# Adafruit_TPS61040_Boost_Converter.net
KiCad netlist of a schematic drawn in Altium Designer
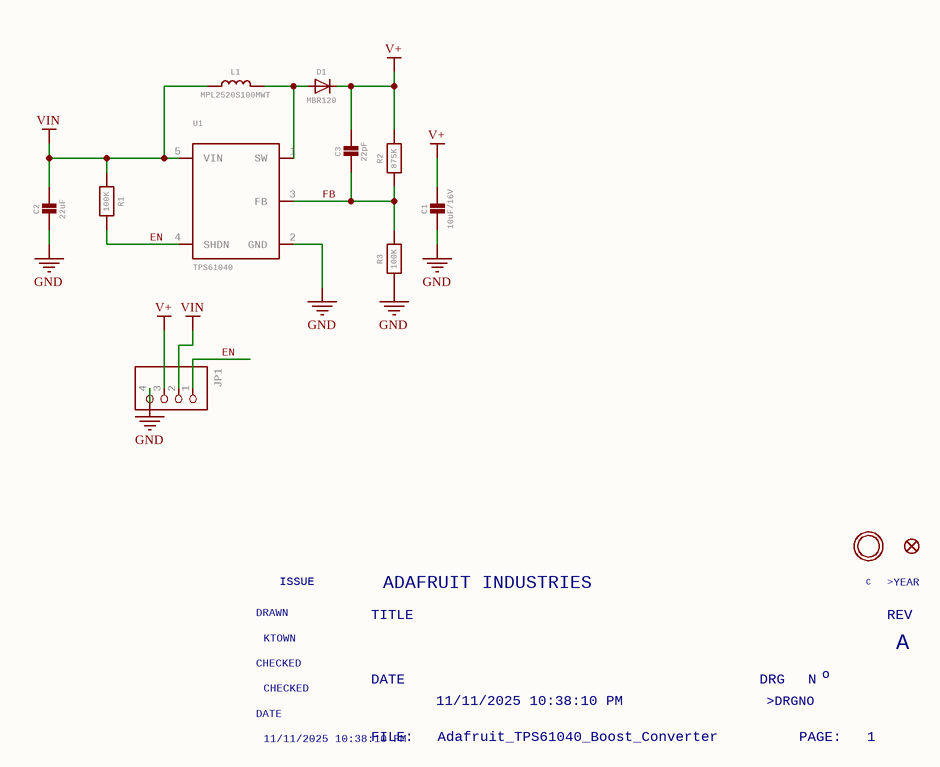
[diagram p0: Adafruit_TPS61040_Boost_Converter.SchDoc]

(export (version "E")
  (design (tool "Eeschema 10.0.6"))
  (components
    (comp (ref "C1")
      (value "10uF/16V")
      (footprint "0805-NO")
      (libsource (lib "microbuilder") (part "CAP_CERAMIC0805-NOOUTLINE"))
    )
    (comp (ref "C2")
      (value "22uF")
      (footprint "0805-NO")
      (libsource (lib "microbuilder") (part "CAP_CERAMIC0805-NOOUTLINE"))
    )
    (comp (ref "C3")
      (value "22pF")
      (footprint "0603-NO")
      (libsource (lib "microbuilder") (part "CAP_CERAMIC0603_NO"))
    )
    (comp (ref "D1")
      (value "MBR120")
      (footprint "SOD-123FL")
      (libsource (lib "microbuilder") (part "DIODE_MINISOD123"))
    )
    (comp (ref "FID1")
      (value "FIDUCIAL_1MM")
      (footprint "FIDUCIAL_1MM")
      (description "Fiducial Alignment Points   Various fiducial points for machine vision alignment.")
      (libsource (lib "microbuilder") (part "FIDUCIAL_1MM"))
    )
    (comp (ref "JP1")
      (value "HEADER-1X4ROUND")
      (footprint "1X04_ROUND")
      (description "PIN HEADER")
      (libsource (lib "microbuilder") (part "HEADER-1X4ROUND"))
    )
    (comp (ref "L1")
      (value "MPL2520S100MWT")
      (footprint "INDUCTOR_1007")
      (libsource (lib "microbuilder") (part "INDUCTOR"))
    )
    (comp (ref "R1")
      (value "100K")
      (footprint "0603-NO")
      (libsource (lib "microbuilder") (part "RESISTOR_0603_NOOUT"))
    )
    (comp (ref "R2")
      (value "875K")
      (footprint "0603-NO")
      (libsource (lib "microbuilder") (part "RESISTOR_0603_NOOUT"))
    )
    (comp (ref "R3")
      (value "100K")
      (footprint "0603-NO")
      (libsource (lib "microbuilder") (part "RESISTOR_0603_NOOUT"))
    )
    (comp (ref "U$9")
      (value "MOUNTINGHOLE2.5")
      (footprint "MOUNTINGHOLE_2.5_PLATED")
      (description "Mounting Hole   For #2 screws (0.086\"/2.18mm width, 0.094\"/2.4mm hole) use 2.5mm")
      (libsource (lib "microbuilder") (part "MOUNTINGHOLE2.5"))
    )
    (comp (ref "U1")
      (value "TPS61040")
      (footprint "SOT23-5")
      (description "FAN5331 - LED/OLED 20V Boost Converter   Digikey: FAN5331SXCT-ND")
      (libsource (lib "adafruit_power") (part "VREG_FAN5331"))
    )
  )
  (nets
    (net (code "1") (name "/EN") (class "Default")
      (node (ref "JP1") (pin "1") (pinfunction "1_1") (pintype "passive"))
      (node (ref "R1") (pin "2") (pinfunction "2_2") (pintype "passive"))
      (node (ref "U1") (pin "4") (pinfunction "SHDN_4") (pintype "bidirectional"))
    )
    (net (code "2") (name "/FB") (class "Default")
      (node (ref "C3") (pin "2") (pinfunction "2_2") (pintype "passive"))
      (node (ref "R2") (pin "1") (pinfunction "1_1") (pintype "passive"))
      (node (ref "R3") (pin "2") (pinfunction "2_2") (pintype "passive"))
      (node (ref "U1") (pin "3") (pinfunction "FB_3") (pintype "bidirectional"))
    )
    (net (code "3") (name "GND") (class "Default")
      (node (ref "C1") (pin "2") (pinfunction "2_2") (pintype "passive"))
      (node (ref "C2") (pin "2") (pinfunction "2_2") (pintype "passive"))
      (node (ref "JP1") (pin "4") (pinfunction "4_4") (pintype "passive"))
      (node (ref "R3") (pin "1") (pinfunction "1_1") (pintype "passive"))
      (node (ref "U1") (pin "2") (pinfunction "GND_2") (pintype "bidirectional"))
    )
    (net (code "4") (name "Net-(L1-2)") (class "Default")
      (node (ref "D1") (pin "A") (pinfunction "A_A") (pintype "passive"))
      (node (ref "L1") (pin "P$2") (pinfunction "2_P$2") (pintype "passive"))
      (node (ref "U1") (pin "1") (pinfunction "SW_1") (pintype "bidirectional"))
    )
    (net (code "5") (name "V+") (class "Default")
      (node (ref "C1") (pin "1") (pinfunction "1_1") (pintype "passive"))
      (node (ref "C3") (pin "1") (pinfunction "1_1") (pintype "passive"))
      (node (ref "D1") (pin "C") (pinfunction "C_C") (pintype "passive"))
      (node (ref "JP1") (pin "3") (pinfunction "3_3") (pintype "passive"))
      (node (ref "R2") (pin "2") (pinfunction "2_2") (pintype "passive"))
    )
    (net (code "6") (name "VIN") (class "Default")
      (node (ref "C2") (pin "1") (pinfunction "1_1") (pintype "passive"))
      (node (ref "JP1") (pin "2") (pinfunction "2_2") (pintype "passive"))
      (node (ref "L1") (pin "P$1") (pinfunction "1_P$1") (pintype "passive"))
      (node (ref "R1") (pin "1") (pinfunction "1_1") (pintype "passive"))
      (node (ref "U1") (pin "5") (pinfunction "VIN_5") (pintype "bidirectional"))
    )
  )
)
